# Modulo_Actuador.net
KiCad netlist of a schematic drawn in EAGLE
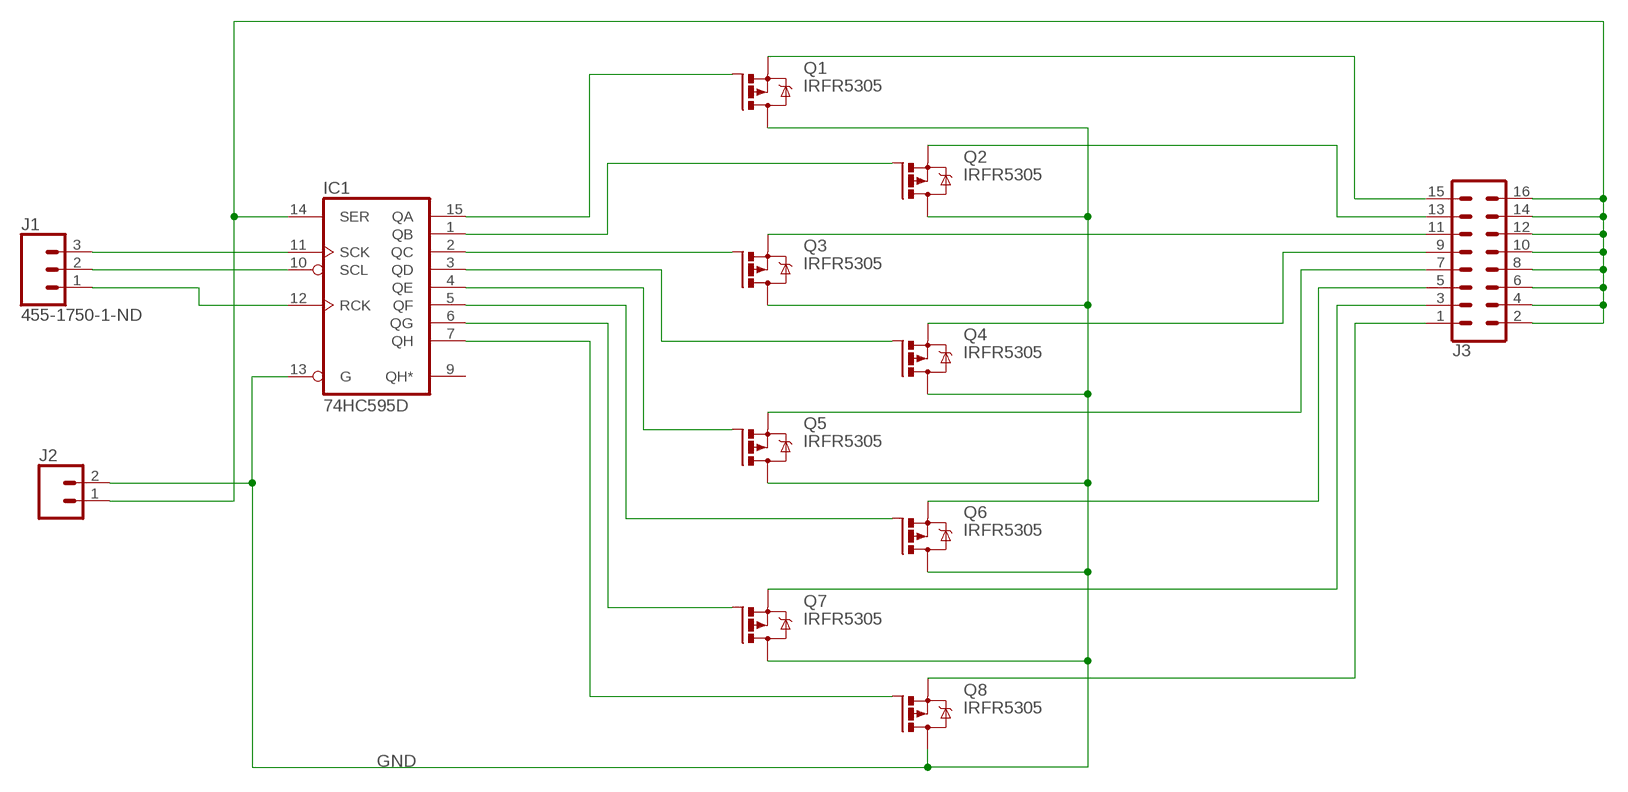
[diagram p0: schematic, sheet 1]

(export (version "E")
  (design (tool "Eeschema 10.0.6"))
  (components
    (comp (ref "IC1")
      (value "74HC595D")
      (footprint "eagle-import:SO16")
      (libsource (lib "eagle-import") (part "74595DHC"))
    )
    (comp (ref "J1")
      (value "455-1750-1-ND")
      (footprint "eagle-import:1X03")
      (libsource (lib "eagle-import") (part "CONN_03"))
    )
    (comp (ref "J2")
      (value "CONN_02")
      (footprint "eagle-import:1X02")
      (libsource (lib "eagle-import") (part "CONN_02"))
    )
    (comp (ref "J3")
      (value "CONN_08X2_HEADER")
      (footprint "eagle-import:2X8")
      (libsource (lib "eagle-import") (part "CONN_08X2_HEADER"))
    )
    (comp (ref "Q1")
      (value "IRFR5305")
      (footprint "eagle-import:D-PAK_TO252AA")
      (libsource (lib "eagle-import") (part "IRF?5305R"))
    )
    (comp (ref "Q2")
      (value "IRFR5305")
      (footprint "eagle-import:D-PAK_TO252AA")
      (libsource (lib "eagle-import") (part "IRF?5305R"))
    )
    (comp (ref "Q3")
      (value "IRFR5305")
      (footprint "eagle-import:D-PAK_TO252AA")
      (libsource (lib "eagle-import") (part "IRF?5305R"))
    )
    (comp (ref "Q4")
      (value "IRFR5305")
      (footprint "eagle-import:D-PAK_TO252AA")
      (libsource (lib "eagle-import") (part "IRF?5305R"))
    )
    (comp (ref "Q5")
      (value "IRFR5305")
      (footprint "eagle-import:D-PAK_TO252AA")
      (libsource (lib "eagle-import") (part "IRF?5305R"))
    )
    (comp (ref "Q6")
      (value "IRFR5305")
      (footprint "eagle-import:D-PAK_TO252AA")
      (libsource (lib "eagle-import") (part "IRF?5305R"))
    )
    (comp (ref "Q7")
      (value "IRFR5305")
      (footprint "eagle-import:D-PAK_TO252AA")
      (libsource (lib "eagle-import") (part "IRF?5305R"))
    )
    (comp (ref "Q8")
      (value "IRFR5305")
      (footprint "eagle-import:D-PAK_TO252AA")
      (libsource (lib "eagle-import") (part "IRF?5305R"))
    )
  )
  (nets
    (net (code "1") (name "/GND") (class "Default")
      (node (ref "IC1") (pin "13") (pinfunction "G_13") (pintype "input"))
      (node (ref "J2") (pin "2") (pinfunction "2_2") (pintype "passive"))
      (node (ref "Q1") (pin "4") (pinfunction "D_4") (pintype "passive"))
      (node (ref "Q2") (pin "4") (pinfunction "D_4") (pintype "passive"))
      (node (ref "Q3") (pin "4") (pinfunction "D_4") (pintype "passive"))
      (node (ref "Q4") (pin "4") (pinfunction "D_4") (pintype "passive"))
      (node (ref "Q5") (pin "4") (pinfunction "D_4") (pintype "passive"))
      (node (ref "Q6") (pin "4") (pinfunction "D_4") (pintype "passive"))
      (node (ref "Q7") (pin "4") (pinfunction "D_4") (pintype "passive"))
      (node (ref "Q8") (pin "4") (pinfunction "D_4") (pintype "passive"))
    )
    (net (code "2") (name "Net-(IC1A-QA)") (class "Default")
      (node (ref "IC1") (pin "15") (pinfunction "QA_15") (pintype "tri_state"))
      (node (ref "Q1") (pin "1") (pinfunction "G_1") (pintype "passive"))
    )
    (net (code "3") (name "Net-(IC1A-QB)") (class "Default")
      (node (ref "IC1") (pin "1") (pinfunction "QB_1") (pintype "tri_state"))
      (node (ref "Q2") (pin "1") (pinfunction "G_1") (pintype "passive"))
    )
    (net (code "4") (name "Net-(IC1A-QC)") (class "Default")
      (node (ref "IC1") (pin "2") (pinfunction "QC_2") (pintype "tri_state"))
      (node (ref "Q3") (pin "1") (pinfunction "G_1") (pintype "passive"))
    )
    (net (code "5") (name "Net-(IC1A-QD)") (class "Default")
      (node (ref "IC1") (pin "3") (pinfunction "QD_3") (pintype "tri_state"))
      (node (ref "Q4") (pin "1") (pinfunction "G_1") (pintype "passive"))
    )
    (net (code "6") (name "Net-(IC1A-QE)") (class "Default")
      (node (ref "IC1") (pin "4") (pinfunction "QE_4") (pintype "tri_state"))
      (node (ref "Q5") (pin "1") (pinfunction "G_1") (pintype "passive"))
    )
    (net (code "7") (name "Net-(IC1A-QF)") (class "Default")
      (node (ref "IC1") (pin "5") (pinfunction "QF_5") (pintype "tri_state"))
      (node (ref "Q6") (pin "1") (pinfunction "G_1") (pintype "passive"))
    )
    (net (code "8") (name "Net-(IC1A-QG)") (class "Default")
      (node (ref "IC1") (pin "6") (pinfunction "QG_6") (pintype "tri_state"))
      (node (ref "Q7") (pin "1") (pinfunction "G_1") (pintype "passive"))
    )
    (net (code "9") (name "Net-(IC1A-QH)") (class "Default")
      (node (ref "IC1") (pin "7") (pinfunction "QH_7") (pintype "tri_state"))
      (node (ref "Q8") (pin "1") (pinfunction "G_1") (pintype "passive"))
    )
    (net (code "10") (name "Net-(IC1A-RCK)") (class "Default")
      (node (ref "IC1") (pin "12") (pinfunction "RCK_12") (pintype "input"))
      (node (ref "J1") (pin "1") (pinfunction "1_1") (pintype "passive"))
    )
    (net (code "11") (name "Net-(IC1A-SCK)") (class "Default")
      (node (ref "IC1") (pin "11") (pinfunction "SCK_11") (pintype "input"))
      (node (ref "J1") (pin "3") (pinfunction "3_3") (pintype "passive"))
    )
    (net (code "12") (name "Net-(IC1A-SCL)") (class "Default")
      (node (ref "IC1") (pin "10") (pinfunction "SCL_10") (pintype "input"))
      (node (ref "J1") (pin "2") (pinfunction "2_2") (pintype "passive"))
    )
    (net (code "13") (name "Net-(IC1A-SER)") (class "Default")
      (node (ref "IC1") (pin "14") (pinfunction "SER_14") (pintype "input"))
      (node (ref "J2") (pin "1") (pinfunction "1_1") (pintype "passive"))
      (node (ref "J3") (pin "10") (pinfunction "10_10") (pintype "passive"))
      (node (ref "J3") (pin "12") (pinfunction "12_12") (pintype "passive"))
      (node (ref "J3") (pin "14") (pinfunction "14_14") (pintype "passive"))
      (node (ref "J3") (pin "16") (pinfunction "16_16") (pintype "passive"))
      (node (ref "J3") (pin "2") (pinfunction "2_2") (pintype "passive"))
      (node (ref "J3") (pin "4") (pinfunction "4_4") (pintype "passive"))
      (node (ref "J3") (pin "6") (pinfunction "6_6") (pintype "passive"))
      (node (ref "J3") (pin "8") (pinfunction "8_8") (pintype "passive"))
    )
    (net (code "14") (name "Net-(Q1-S)") (class "Default")
      (node (ref "J3") (pin "15") (pinfunction "15_15") (pintype "passive"))
      (node (ref "Q1") (pin "3") (pinfunction "S_3") (pintype "passive"))
    )
    (net (code "15") (name "Net-(Q2-S)") (class "Default")
      (node (ref "J3") (pin "13") (pinfunction "13_13") (pintype "passive"))
      (node (ref "Q2") (pin "3") (pinfunction "S_3") (pintype "passive"))
    )
    (net (code "16") (name "Net-(Q3-S)") (class "Default")
      (node (ref "J3") (pin "11") (pinfunction "11_11") (pintype "passive"))
      (node (ref "Q3") (pin "3") (pinfunction "S_3") (pintype "passive"))
    )
    (net (code "17") (name "Net-(Q4-S)") (class "Default")
      (node (ref "J3") (pin "9") (pinfunction "9_9") (pintype "passive"))
      (node (ref "Q4") (pin "3") (pinfunction "S_3") (pintype "passive"))
    )
    (net (code "18") (name "Net-(Q5-S)") (class "Default")
      (node (ref "J3") (pin "7") (pinfunction "7_7") (pintype "passive"))
      (node (ref "Q5") (pin "3") (pinfunction "S_3") (pintype "passive"))
    )
    (net (code "19") (name "Net-(Q6-S)") (class "Default")
      (node (ref "J3") (pin "5") (pinfunction "5_5") (pintype "passive"))
      (node (ref "Q6") (pin "3") (pinfunction "S_3") (pintype "passive"))
    )
    (net (code "20") (name "Net-(Q7-S)") (class "Default")
      (node (ref "J3") (pin "3") (pinfunction "3_3") (pintype "passive"))
      (node (ref "Q7") (pin "3") (pinfunction "S_3") (pintype "passive"))
    )
    (net (code "21") (name "Net-(Q8-S)") (class "Default")
      (node (ref "J3") (pin "1") (pinfunction "1_1") (pintype "passive"))
      (node (ref "Q8") (pin "3") (pinfunction "S_3") (pintype "passive"))
    )
    (net (code "22") (name "unconnected-(IC1A-QH*-Pad9)") (class "Default")
      (node (ref "IC1") (pin "9") (pinfunction "QH*_9") (pintype "tri_state"))
    )
  )
)
